# STM32F100_Base_Wireless_1.net
KiCad netlist of a schematic drawn in EAGLE
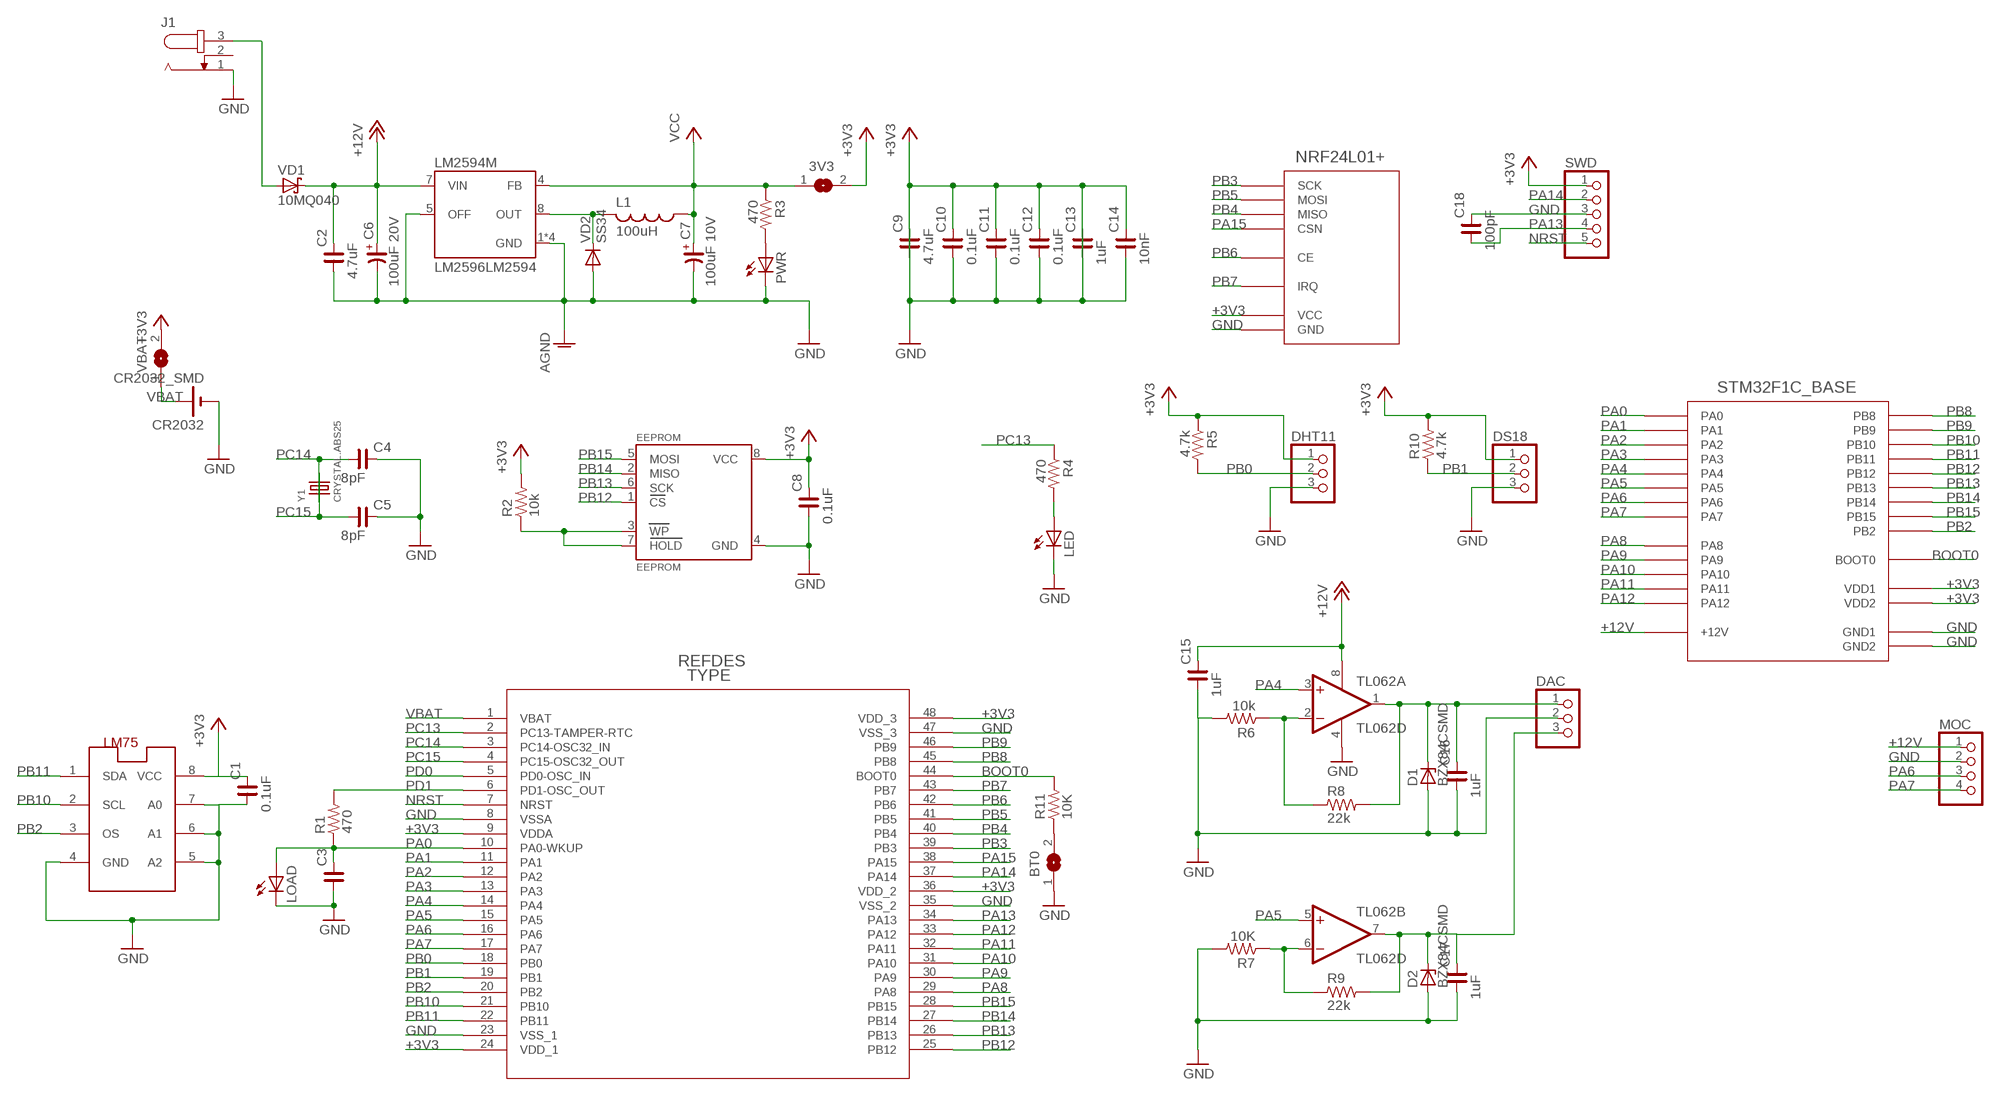
[diagram p0: schematic, sheet 1]

(export (version "E")
  (design (tool "Eeschema 10.0.6"))
  (components
    (comp (ref "3V3") (value "SJ") (footprint "eagle-import:SJ") (libsource (lib "eagle-import") (part "SJ")))
    (comp (ref "BT0") (value "SJ") (footprint "eagle-import:SJ") (libsource (lib "eagle-import") (part "SJ")))
    (comp (ref "C1")
      (value "0.1uF")
      (footprint "eagle-import:C0603")
      (libsource (lib "eagle-import") (part "C_0603"))
    )
    (comp (ref "C2")
      (value "4.7uF")
      (footprint "eagle-import:C0603")
      (libsource (lib "eagle-import") (part "C_0603"))
    )
    (comp (ref "C3")
      (value "C_0603")
      (footprint "eagle-import:C0603")
      (libsource (lib "eagle-import") (part "C_0603"))
    )
    (comp (ref "C4")
      (value "8pF")
      (footprint "eagle-import:C0603")
      (libsource (lib "eagle-import") (part "C_0603"))
    )
    (comp (ref "C5")
      (value "8pF")
      (footprint "eagle-import:C0603")
      (libsource (lib "eagle-import") (part "C_0603"))
    )
    (comp (ref "C6")
      (value "100uF 20V")
      (footprint "eagle-import:C7343_T")
      (libsource (lib "eagle-import") (part "CP_7343"))
    )
    (comp (ref "C7")
      (value "100uF 10V")
      (footprint "eagle-import:C6032-28_T")
      (libsource (lib "eagle-import") (part "CP_6032-28"))
    )
    (comp (ref "C8")
      (value "0.1uF")
      (footprint "eagle-import:C0603")
      (libsource (lib "eagle-import") (part "C_0603"))
    )
    (comp (ref "C9")
      (value "4.7uF")
      (footprint "eagle-import:C0603")
      (libsource (lib "eagle-import") (part "C_0603"))
    )
    (comp (ref "C10")
      (value "0.1uF")
      (footprint "eagle-import:C0603")
      (libsource (lib "eagle-import") (part "C_0603"))
    )
    (comp (ref "C11")
      (value "0.1uF")
      (footprint "eagle-import:C0603")
      (libsource (lib "eagle-import") (part "C_0603"))
    )
    (comp (ref "C12")
      (value "0.1uF")
      (footprint "eagle-import:C0603")
      (libsource (lib "eagle-import") (part "C_0603"))
    )
    (comp (ref "C13")
      (value "1uF")
      (footprint "eagle-import:C0603")
      (libsource (lib "eagle-import") (part "C_0603"))
    )
    (comp (ref "C14")
      (value "10nF")
      (footprint "eagle-import:C0603")
      (libsource (lib "eagle-import") (part "C_0603"))
    )
    (comp (ref "C15")
      (value "1uF")
      (footprint "eagle-import:C0603")
      (libsource (lib "eagle-import") (part "C_0603"))
    )
    (comp (ref "C16")
      (value "1uF")
      (footprint "eagle-import:C0603")
      (libsource (lib "eagle-import") (part "C_0603"))
    )
    (comp (ref "C17")
      (value "1uF")
      (footprint "eagle-import:C0603")
      (libsource (lib "eagle-import") (part "C_0603"))
    )
    (comp (ref "C18")
      (value "100pF")
      (footprint "eagle-import:C0603")
      (libsource (lib "eagle-import") (part "C_0603"))
    )
    (comp (ref "CR2032")
      (value "CR2032_SMD")
      (footprint "eagle-import:SMD_BH-2")
      (libsource (lib "eagle-import") (part "CR2032_SMD"))
    )
    (comp (ref "D1")
      (value "BZX84CSMD")
      (footprint "eagle-import:TO236")
      (libsource (lib "eagle-import") (part "BZX84CSMD"))
    )
    (comp (ref "D2")
      (value "BZX84CSMD")
      (footprint "eagle-import:TO236")
      (libsource (lib "eagle-import") (part "BZX84CSMD"))
    )
    (comp (ref "DAC")
      (value "PINHD-1X03_2.54-S")
      (footprint "eagle-import:1X03-S")
      (libsource (lib "eagle-import") (part "PINHD-1X03_2.54-S"))
    )
    (comp (ref "DHT11")
      (value "PINHD-1X03_2.54-S")
      (footprint "eagle-import:1X03-S")
      (libsource (lib "eagle-import") (part "PINHD-1X03_2.54-S"))
    )
    (comp (ref "DS18")
      (value "PINHD-1X03_2.54-S")
      (footprint "eagle-import:1X03-S")
      (libsource (lib "eagle-import") (part "PINHD-1X03_2.54-S"))
    )
    (comp (ref "EEPROM")
      (value "EEPROM")
      (footprint "eagle-import:SOIC8_150MIL")
      (libsource (lib "eagle-import") (part "EEPROM_SPI_AT25040A"))
    )
    (comp (ref "J1")
      (value "JACK-PLUG0")
      (footprint "eagle-import:SPC4077")
      (libsource (lib "eagle-import") (part "JACK-PLUG0"))
    )
    (comp (ref "L1")
      (value "100uH")
      (footprint "eagle-import:POWER-CHOKE_WE-TPC")
      (libsource (lib "eagle-import") (part "L-USWE-TPC"))
    )
    (comp (ref "LED")
      (value "LEDCHIPLED_1206")
      (footprint "eagle-import:CHIPLED_1206")
      (libsource (lib "eagle-import") (part "LEDCHIPLED_1206"))
    )
    (comp (ref "LM75")
      (value "LM75_ICN")
      (footprint "eagle-import:SO8_LM75")
      (libsource (lib "eagle-import") (part "LM75_ICN"))
    )
    (comp (ref "LM2594M")
      (value "LM2596LM2594")
      (footprint "eagle-import:SOIC8_150MIL")
      (libsource (lib "eagle-import") (part "LM2596LM2594"))
    )
    (comp (ref "LOAD")
      (value "LEDCHIPLED_1206")
      (footprint "eagle-import:CHIPLED_1206")
      (libsource (lib "eagle-import") (part "LEDCHIPLED_1206"))
    )
    (comp (ref "MOC")
      (value "PINHD-1X04_2.54-S")
      (footprint "eagle-import:1X04-S")
      (libsource (lib "eagle-import") (part "PINHD-1X04_2.54-S"))
    )
    (comp (ref "NRF24L01+")
      (value "NRF24L01+")
      (footprint "eagle-import:NRF24L01+")
      (libsource (lib "eagle-import") (part "NRF24L01+"))
    )
    (comp (ref "PWR")
      (value "LEDCHIPLED_1206")
      (footprint "eagle-import:CHIPLED_1206")
      (libsource (lib "eagle-import") (part "LEDCHIPLED_1206"))
    )
    (comp (ref "R1")
      (value "470")
      (footprint "eagle-import:R1206")
      (libsource (lib "eagle-import") (part "R_1206"))
    )
    (comp (ref "R2")
      (value "10k")
      (footprint "eagle-import:R1206")
      (libsource (lib "eagle-import") (part "R_1206"))
    )
    (comp (ref "R3")
      (value "470")
      (footprint "eagle-import:R1206")
      (libsource (lib "eagle-import") (part "R_1206"))
    )
    (comp (ref "R4")
      (value "470")
      (footprint "eagle-import:R1206")
      (libsource (lib "eagle-import") (part "R_1206"))
    )
    (comp (ref "R5")
      (value "4.7k")
      (footprint "eagle-import:R1206")
      (libsource (lib "eagle-import") (part "R_1206"))
    )
    (comp (ref "R6")
      (value "10k")
      (footprint "eagle-import:R1206")
      (libsource (lib "eagle-import") (part "R_1206"))
    )
    (comp (ref "R7")
      (value "10K")
      (footprint "eagle-import:R1206")
      (libsource (lib "eagle-import") (part "R_1206"))
    )
    (comp (ref "R8")
      (value "22k")
      (footprint "eagle-import:R1206")
      (libsource (lib "eagle-import") (part "R_1206"))
    )
    (comp (ref "R9")
      (value "22k")
      (footprint "eagle-import:R1206")
      (libsource (lib "eagle-import") (part "R_1206"))
    )
    (comp (ref "R10")
      (value "4.7k")
      (footprint "eagle-import:R1206")
      (libsource (lib "eagle-import") (part "R_1206"))
    )
    (comp (ref "R11")
      (value "10K")
      (footprint "eagle-import:R1206")
      (libsource (lib "eagle-import") (part "R_1206"))
    )
    (comp (ref "STM32F100C")
      (value "STM32F100C8T6B")
      (footprint "eagle-import:LQFP-48")
      (libsource (lib "eagle-import") (part "STM32F100C8T6B"))
    )
    (comp (ref "SWD")
      (value "PINHD-1X05_2.54-90°-S")
      (footprint "eagle-import:1X05_90-S")
      (libsource (lib "eagle-import") (part "PINHD-1X05_2.54-90°-S"))
    )
    (comp (ref "TL062")
      (value "TL062D")
      (footprint "eagle-import:SO08")
      (libsource (lib "eagle-import") (part "TL062D"))
    )
    (comp (ref "U$1")
      (value "STM32F1C_BASE")
      (footprint "eagle-import:STM32F1_BASE")
      (libsource (lib "eagle-import") (part "STM32F1C_BASE"))
    )
    (comp (ref "VBAT")
      (value "SJ")
      (footprint "eagle-import:SJ")
      (libsource (lib "eagle-import") (part "SJ"))
    )
    (comp (ref "VD1")
      (value "10MQ040")
      (footprint "eagle-import:SMA")
      (libsource (lib "eagle-import") (part "10MQ040"))
    )
    (comp (ref "VD2")
      (value "SS34")
      (footprint "eagle-import:DO214AC")
      (libsource (lib "eagle-import") (part "DIODE-DO214AC"))
    )
    (comp (ref "Y1")
      (value "CRYSTAL.ABS25")
      (footprint "eagle-import:ABS25")
      (libsource (lib "eagle-import") (part "CRYSTAL.ABS25"))
    )
  )
  (nets
    (net (code "1") (name "+3V3") (class "Default")
      (node (ref "3V3") (pin "2") (pinfunction "2_2") (pintype "passive"))
      (node (ref "C1") (pin "2") (pinfunction "2_2") (pintype "passive"))
      (node (ref "C10") (pin "2") (pinfunction "2_2") (pintype "passive"))
      (node (ref "C11") (pin "2") (pinfunction "2_2") (pintype "passive"))
      (node (ref "C12") (pin "2") (pinfunction "2_2") (pintype "passive"))
      (node (ref "C13") (pin "1") (pinfunction "1_1") (pintype "passive"))
      (node (ref "C14") (pin "2") (pinfunction "2_2") (pintype "passive"))
      (node (ref "C8") (pin "2") (pinfunction "2_2") (pintype "passive"))
      (node (ref "C9") (pin "1") (pinfunction "1_1") (pintype "passive"))
      (node (ref "DHT11") (pin "1") (pinfunction "1_1") (pintype "passive"))
      (node (ref "DS18") (pin "1") (pinfunction "1_1") (pintype "passive"))
      (node (ref "EEPROM") (pin "8") (pinfunction "VCC_8") (pintype "power_in"))
      (node (ref "LM75") (pin "8") (pinfunction "VCC_8") (pintype "power_in"))
      (node (ref "NRF24L01+") (pin "VCC") (pinfunction "VCC_VCC") (pintype "passive"))
      (node (ref "R10") (pin "2") (pinfunction "2_2") (pintype "passive"))
      (node (ref "R2") (pin "2") (pinfunction "2_2") (pintype "passive"))
      (node (ref "R5") (pin "1") (pinfunction "1_1") (pintype "passive"))
      (node (ref "STM32F100C") (pin "24") (pinfunction "VDD_1_24") (pintype "passive"))
      (node (ref "STM32F100C") (pin "36") (pinfunction "VDD_2_36") (pintype "passive"))
      (node (ref "STM32F100C") (pin "48") (pinfunction "VDD_3_48") (pintype "passive"))
      (node (ref "STM32F100C") (pin "9") (pinfunction "VDDA_9") (pintype "passive"))
      (node (ref "SWD") (pin "1") (pinfunction "1_1") (pintype "passive"))
      (node (ref "U$1") (pin "3.3") (pinfunction "VDD1_3.3") (pintype "power_in"))
      (node (ref "U$1") (pin "3.3_1") (pinfunction "VDD2_3.3_1") (pintype "power_in"))
      (node (ref "VBAT") (pin "2") (pinfunction "2_2") (pintype "passive"))
    )
    (net (code "2") (name "+12V") (class "Default")
      (node (ref "C15") (pin "2") (pinfunction "2_2") (pintype "passive"))
      (node (ref "C2") (pin "2") (pinfunction "2_2") (pintype "passive"))
      (node (ref "C6") (pin "+") (pinfunction "+_+") (pintype "passive"))
      (node (ref "LM2594M") (pin "7") (pinfunction "VIN_7") (pintype "power_in"))
      (node (ref "MOC") (pin "1") (pinfunction "1_1") (pintype "passive"))
      (node (ref "TL062") (pin "8") (pinfunction "V+_8") (pintype "power_in"))
      (node (ref "U$1") (pin "+12") (pinfunction "+12V_+12") (pintype "power_in"))
      (node (ref "VD1") (pin "C") (pinfunction "C_C") (pintype "passive"))
    )
    (net (code "3") (name "/BOOT0") (class "Default")
      (node (ref "R11") (pin "2") (pinfunction "2_2") (pintype "passive"))
      (node (ref "STM32F100C") (pin "44") (pinfunction "BOOT0_44") (pintype "passive"))
      (node (ref "U$1") (pin "BOOT0") (pinfunction "BOOT0_BOOT0") (pintype "passive"))
    )
    (net (code "4") (name "/NRST") (class "Default")
      (node (ref "STM32F100C") (pin "7") (pinfunction "NRST_7") (pintype "passive"))
      (node (ref "SWD") (pin "5") (pinfunction "5_5") (pintype "passive"))
    )
    (net (code "5") (name "/PA0") (class "Default")
      (node (ref "C3") (pin "2") (pinfunction "2_2") (pintype "passive"))
      (node (ref "LOAD") (pin "A") (pinfunction "A_A") (pintype "passive"))
      (node (ref "R1") (pin "1") (pinfunction "1_1") (pintype "passive"))
      (node (ref "STM32F100C") (pin "10") (pinfunction "PA0-WKUP_10") (pintype "passive"))
      (node (ref "U$1") (pin "PA0") (pinfunction "PA0_PA0") (pintype "passive"))
    )
    (net (code "6") (name "/PA1") (class "Default")
      (node (ref "STM32F100C") (pin "11") (pinfunction "PA1_11") (pintype "passive"))
      (node (ref "U$1") (pin "PA1") (pinfunction "PA1_PA1") (pintype "passive"))
    )
    (net (code "7") (name "/PA2") (class "Default")
      (node (ref "STM32F100C") (pin "12") (pinfunction "PA2_12") (pintype "passive"))
      (node (ref "U$1") (pin "PA2") (pinfunction "PA2_PA2") (pintype "passive"))
    )
    (net (code "8") (name "/PA3") (class "Default")
      (node (ref "STM32F100C") (pin "13") (pinfunction "PA3_13") (pintype "passive"))
      (node (ref "U$1") (pin "PA3") (pinfunction "PA3_PA3") (pintype "passive"))
    )
    (net (code "9") (name "/PA4") (class "Default")
      (node (ref "STM32F100C") (pin "14") (pinfunction "PA4_14") (pintype "passive"))
      (node (ref "TL062") (pin "3") (pinfunction "+IN_3") (pintype "input"))
      (node (ref "U$1") (pin "PA4") (pinfunction "PA4_PA4") (pintype "passive"))
    )
    (net (code "10") (name "/PA5") (class "Default")
      (node (ref "STM32F100C") (pin "15") (pinfunction "PA5_15") (pintype "passive"))
      (node (ref "TL062") (pin "5") (pinfunction "+IN_5") (pintype "input"))
      (node (ref "U$1") (pin "PA5") (pinfunction "PA5_PA5") (pintype "passive"))
    )
    (net (code "11") (name "/PA6") (class "Default")
      (node (ref "MOC") (pin "3") (pinfunction "3_3") (pintype "passive"))
      (node (ref "STM32F100C") (pin "16") (pinfunction "PA6_16") (pintype "passive"))
      (node (ref "U$1") (pin "PA6") (pinfunction "PA6_PA6") (pintype "passive"))
    )
    (net (code "12") (name "/PA7") (class "Default")
      (node (ref "MOC") (pin "4") (pinfunction "4_4") (pintype "passive"))
      (node (ref "STM32F100C") (pin "17") (pinfunction "PA7_17") (pintype "passive"))
      (node (ref "U$1") (pin "PA7") (pinfunction "PA7_PA7") (pintype "passive"))
    )
    (net (code "13") (name "/PA8") (class "Default")
      (node (ref "STM32F100C") (pin "29") (pinfunction "PA8_29") (pintype "passive"))
      (node (ref "U$1") (pin "PA8") (pinfunction "PA8_PA8") (pintype "passive"))
    )
    (net (code "14") (name "/PA9") (class "Default")
      (node (ref "STM32F100C") (pin "30") (pinfunction "PA9_30") (pintype "passive"))
      (node (ref "U$1") (pin "PA9") (pinfunction "PA9_PA9") (pintype "passive"))
    )
    (net (code "15") (name "/PA10") (class "Default")
      (node (ref "STM32F100C") (pin "31") (pinfunction "PA10_31") (pintype "passive"))
      (node (ref "U$1") (pin "PA10") (pinfunction "PA10_PA10") (pintype "passive"))
    )
    (net (code "16") (name "/PA11") (class "Default")
      (node (ref "STM32F100C") (pin "32") (pinfunction "PA11_32") (pintype "passive"))
      (node (ref "U$1") (pin "PA11") (pinfunction "PA11_PA11") (pintype "passive"))
    )
    (net (code "17") (name "/PA12") (class "Default")
      (node (ref "STM32F100C") (pin "33") (pinfunction "PA12_33") (pintype "passive"))
      (node (ref "U$1") (pin "PA12") (pinfunction "PA12_PA12") (pintype "passive"))
    )
    (net (code "18") (name "/PA13") (class "Default")
      (node (ref "C18") (pin "1") (pinfunction "1_1") (pintype "passive"))
      (node (ref "STM32F100C") (pin "34") (pinfunction "PA13_34") (pintype "passive"))
      (node (ref "SWD") (pin "4") (pinfunction "4_4") (pintype "passive"))
    )
    (net (code "19") (name "/PA14") (class "Default")
      (node (ref "STM32F100C") (pin "37") (pinfunction "PA14_37") (pintype "passive"))
      (node (ref "SWD") (pin "2") (pinfunction "2_2") (pintype "passive"))
    )
    (net (code "20") (name "/PA15") (class "Default")
      (node (ref "NRF24L01+") (pin "CSN") (pinfunction "CSN_CSN") (pintype "passive"))
      (node (ref "STM32F100C") (pin "38") (pinfunction "PA15_38") (pintype "passive"))
    )
    (net (code "21") (name "/PB0") (class "Default")
      (node (ref "DHT11") (pin "2") (pinfunction "2_2") (pintype "passive"))
      (node (ref "R5") (pin "2") (pinfunction "2_2") (pintype "passive"))
      (node (ref "STM32F100C") (pin "18") (pinfunction "PB0_18") (pintype "passive"))
    )
    (net (code "22") (name "/PB1") (class "Default")
      (node (ref "DS18") (pin "2") (pinfunction "2_2") (pintype "passive"))
      (node (ref "R10") (pin "1") (pinfunction "1_1") (pintype "passive"))
      (node (ref "STM32F100C") (pin "19") (pinfunction "PB1_19") (pintype "passive"))
    )
    (net (code "23") (name "/PB2") (class "Default")
      (node (ref "LM75") (pin "3") (pinfunction "OS_3") (pintype "output"))
      (node (ref "STM32F100C") (pin "20") (pinfunction "PB2_20") (pintype "passive"))
      (node (ref "U$1") (pin "B2") (pinfunction "PB2_B2") (pintype "passive"))
    )
    (net (code "24") (name "/PB3") (class "Default")
      (node (ref "NRF24L01+") (pin "SCK") (pinfunction "SCK_SCK") (pintype "passive"))
      (node (ref "STM32F100C") (pin "39") (pinfunction "PB3_39") (pintype "passive"))
    )
    (net (code "25") (name "/PB4") (class "Default")
      (node (ref "NRF24L01+") (pin "MISO") (pinfunction "MISO_MISO") (pintype "passive"))
      (node (ref "STM32F100C") (pin "40") (pinfunction "PB4_40") (pintype "passive"))
    )
    (net (code "26") (name "/PB5") (class "Default")
      (node (ref "NRF24L01+") (pin "MOSI") (pinfunction "MOSI_MOSI") (pintype "passive"))
      (node (ref "STM32F100C") (pin "41") (pinfunction "PB5_41") (pintype "passive"))
    )
    (net (code "27") (name "/PB6") (class "Default")
      (node (ref "NRF24L01+") (pin "CE") (pinfunction "CE_CE") (pintype "passive"))
      (node (ref "STM32F100C") (pin "42") (pinfunction "PB6_42") (pintype "passive"))
    )
    (net (code "28") (name "/PB7") (class "Default")
      (node (ref "NRF24L01+") (pin "IRQ") (pinfunction "IRQ_IRQ") (pintype "passive"))
      (node (ref "STM32F100C") (pin "43") (pinfunction "PB7_43") (pintype "passive"))
    )
    (net (code "29") (name "/PB8") (class "Default")
      (node (ref "STM32F100C") (pin "45") (pinfunction "PB8_45") (pintype "passive"))
      (node (ref "U$1") (pin "PB8") (pinfunction "PB8_PB8") (pintype "passive"))
    )
    (net (code "30") (name "/PB9") (class "Default")
      (node (ref "STM32F100C") (pin "46") (pinfunction "PB9_46") (pintype "passive"))
      (node (ref "U$1") (pin "PB9") (pinfunction "PB9_PB9") (pintype "passive"))
    )
    (net (code "31") (name "/PB10") (class "Default")
      (node (ref "LM75") (pin "2") (pinfunction "SCL_2") (pintype "bidirectional"))
      (node (ref "STM32F100C") (pin "21") (pinfunction "PB10_21") (pintype "passive"))
      (node (ref "U$1") (pin "PB10") (pinfunction "PB10_PB10") (pintype "passive"))
    )
    (net (code "32") (name "/PB11") (class "Default")
      (node (ref "LM75") (pin "1") (pinfunction "SDA_1") (pintype "bidirectional"))
      (node (ref "STM32F100C") (pin "22") (pinfunction "PB11_22") (pintype "passive"))
      (node (ref "U$1") (pin "PB11") (pinfunction "PB11_PB11") (pintype "passive"))
    )
    (net (code "33") (name "/PB12") (class "Default")
      (node (ref "EEPROM") (pin "1") (pinfunction "CS_1") (pintype "bidirectional"))
      (node (ref "STM32F100C") (pin "25") (pinfunction "PB12_25") (pintype "passive"))
      (node (ref "U$1") (pin "PB12") (pinfunction "PB12_PB12") (pintype "passive"))
    )
    (net (code "34") (name "/PB13") (class "Default")
      (node (ref "EEPROM") (pin "6") (pinfunction "SCK_6") (pintype "bidirectional"))
      (node (ref "STM32F100C") (pin "26") (pinfunction "PB13_26") (pintype "passive"))
      (node (ref "U$1") (pin "PB13") (pinfunction "PB13_PB13") (pintype "passive"))
    )
    (net (code "35") (name "/PB14") (class "Default")
      (node (ref "EEPROM") (pin "2") (pinfunction "MISO_2") (pintype "bidirectional"))
      (node (ref "STM32F100C") (pin "27") (pinfunction "PB14_27") (pintype "passive"))
      (node (ref "U$1") (pin "PB14") (pinfunction "PB14_PB14") (pintype "passive"))
    )
    (net (code "36") (name "/PB15") (class "Default")
      (node (ref "EEPROM") (pin "5") (pinfunction "MOSI_5") (pintype "bidirectional"))
      (node (ref "STM32F100C") (pin "28") (pinfunction "PB15_28") (pintype "passive"))
      (node (ref "U$1") (pin "PB15") (pinfunction "PB15_PB15") (pintype "passive"))
    )
    (net (code "37") (name "/PC13") (class "Default")
      (node (ref "R4") (pin "1") (pinfunction "1_1") (pintype "passive"))
      (node (ref "STM32F100C") (pin "2") (pinfunction "PC13-TAMPER-RTC_2") (pintype "passive"))
    )
    (net (code "38") (name "/PC14") (class "Default")
      (node (ref "C4") (pin "1") (pinfunction "1_1") (pintype "passive"))
      (node (ref "STM32F100C") (pin "3") (pinfunction "PC14-OSC32_IN_3") (pintype "passive"))
      (node (ref "Y1") (pin "1") (pinfunction "1_1") (pintype "passive"))
    )
    (net (code "39") (name "/PC15") (class "Default")
      (node (ref "C5") (pin "1") (pinfunction "1_1") (pintype "passive"))
      (node (ref "STM32F100C") (pin "4") (pinfunction "PC15-OSC32_OUT_4") (pintype "passive"))
      (node (ref "Y1") (pin "4") (pinfunction "2_4") (pintype "passive"))
    )
    (net (code "40") (name "/PD0") (class "Default")
      (node (ref "STM32F100C") (pin "5") (pinfunction "PD0-OSC_IN_5") (pintype "passive"))
    )
    (net (code "41") (name "/PD1") (class "Default")
      (node (ref "R1") (pin "2") (pinfunction "2_2") (pintype "passive"))
      (node (ref "STM32F100C") (pin "6") (pinfunction "PD1-OSC_OUT_6") (pintype "passive"))
    )
    (net (code "42") (name "/VBAT") (class "Default")
      (node (ref "CR2032") (pin "P$POS1") (pinfunction "+_P$POS1") (pintype "passive"))
      (node (ref "STM32F100C") (pin "1") (pinfunction "VBAT_1") (pintype "passive"))
      (node (ref "VBAT") (pin "1") (pinfunction "1_1") (pintype "passive"))
    )
    (net (code "43") (name "AGND") (class "Default")
      (node (ref "BT0") (pin "1") (pinfunction "1_1") (pintype "passive"))
      (node (ref "C1") (pin "1") (pinfunction "1_1") (pintype "passive"))
      (node (ref "C10") (pin "1") (pinfunction "1_1") (pintype "passive"))
      (node (ref "C11") (pin "1") (pinfunction "1_1") (pintype "passive"))
      (node (ref "C12") (pin "1") (pinfunction "1_1") (pintype "passive"))
      (node (ref "C13") (pin "2") (pinfunction "2_2") (pintype "passive"))
      (node (ref "C14") (pin "1") (pinfunction "1_1") (pintype "passive"))
      (node (ref "C15") (pin "1") (pinfunction "1_1") (pintype "passive"))
      (node (ref "C16") (pin "1") (pinfunction "1_1") (pintype "passive"))
      (node (ref "C17") (pin "1") (pinfunction "1_1") (pintype "passive"))
      (node (ref "C18") (pin "2") (pinfunction "2_2") (pintype "passive"))
      (node (ref "C2") (pin "1") (pinfunction "1_1") (pintype "passive"))
      (node (ref "C3") (pin "1") (pinfunction "1_1") (pintype "passive"))
      (node (ref "C4") (pin "2") (pinfunction "2_2") (pintype "passive"))
      (node (ref "C5") (pin "2") (pinfunction "2_2") (pintype "passive"))
      (node (ref "C6") (pin "-") (pinfunction "-_-") (pintype "passive"))
      (node (ref "C7") (pin "-") (pinfunction "-_-") (pintype "passive"))
      (node (ref "C8") (pin "1") (pinfunction "1_1") (pintype "passive"))
      (node (ref "C9") (pin "2") (pinfunction "2_2") (pintype "passive"))
      (node (ref "CR2032") (pin "P$NEG") (pinfunction "-_P$NEG") (pintype "passive"))
      (node (ref "D1") (pin "A") (pinfunction "A_A") (pintype "passive"))
      (node (ref "D2") (pin "A") (pinfunction "A_A") (pintype "passive"))
      (node (ref "DAC") (pin "2") (pinfunction "2_2") (pintype "passive"))
      (node (ref "DHT11") (pin "3") (pinfunction "3_3") (pintype "passive"))
      (node (ref "DS18") (pin "3") (pinfunction "3_3") (pintype "passive"))
      (node (ref "EEPROM") (pin "4") (pinfunction "GND_4") (pintype "power_in"))
      (node (ref "J1") (pin "1") (pinfunction "1_1") (pintype "passive"))
      (node (ref "LED") (pin "C") (pinfunction "C_C") (pintype "passive"))
      (node (ref "LM2594M") (pin "1") (pinfunction "GND_1") (pintype "power_in"))
      (node (ref "LM2594M") (pin "2") (pinfunction "GND_2") (pintype "power_in"))
      (node (ref "LM2594M") (pin "3") (pinfunction "GND_3") (pintype "power_in"))
      (node (ref "LM2594M") (pin "5") (pinfunction "OFF_5") (pintype "input"))
      (node (ref "LM2594M") (pin "6") (pinfunction "GND_6") (pintype "power_in"))
      (node (ref "LM75") (pin "4") (pinfunction "GND_4") (pintype "power_in"))
      (node (ref "LM75") (pin "5") (pinfunction "A2_5") (pintype "input"))
      (node (ref "LM75") (pin "6") (pinfunction "A1_6") (pintype "input"))
      (node (ref "LM75") (pin "7") (pinfunction "A0_7") (pintype "input"))
      (node (ref "LOAD") (pin "C") (pinfunction "C_C") (pintype "passive"))
      (node (ref "MOC") (pin "2") (pinfunction "2_2") (pintype "passive"))
      (node (ref "NRF24L01+") (pin "GND") (pinfunction "GND_GND") (pintype "passive"))
      (node (ref "PWR") (pin "C") (pinfunction "C_C") (pintype "passive"))
      (node (ref "R6") (pin "2") (pinfunction "2_2") (pintype "passive"))
      (node (ref "R7") (pin "2") (pinfunction "2_2") (pintype "passive"))
      (node (ref "STM32F100C") (pin "23") (pinfunction "VSS_1_23") (pintype "passive"))
      (node (ref "STM32F100C") (pin "35") (pinfunction "VSS_2_35") (pintype "passive"))
      (node (ref "STM32F100C") (pin "47") (pinfunction "VSS_3_47") (pintype "passive"))
      (node (ref "STM32F100C") (pin "8") (pinfunction "VSSA_8") (pintype "passive"))
      (node (ref "SWD") (pin "3") (pinfunction "3_3") (pintype "passive"))
      (node (ref "TL062") (pin "4") (pinfunction "V-_4") (pintype "power_in"))
      (node (ref "U$1") (pin "GND") (pinfunction "GND1_GND") (pintype "power_in"))
      (node (ref "U$1") (pin "GND1") (pinfunction "GND2_GND1") (pintype "power_in"))
      (node (ref "VD2") (pin "A") (pinfunction "A_A") (pintype "passive"))
    )
    (net (code "44") (name "Net-(BT0-Pad2)") (class "Default")
      (node (ref "BT0") (pin "2") (pinfunction "2_2") (pintype "passive"))
      (node (ref "R11") (pin "1") (pinfunction "1_1") (pintype "passive"))
    )
    (net (code "45") (name "Net-(EEPROM-HOLD)") (class "Default")
      (node (ref "EEPROM") (pin "3") (pinfunction "WP_3") (pintype "bidirectional"))
      (node (ref "EEPROM") (pin "7") (pinfunction "HOLD_7") (pintype "bidirectional"))
      (node (ref "R2") (pin "1") (pinfunction "1_1") (pintype "passive"))
    )
    (net (code "46") (name "Net-(J1-Pad3)") (class "Default")
      (node (ref "J1") (pin "3") (pinfunction "3_3") (pintype "passive"))
      (node (ref "VD1") (pin "A") (pinfunction "A_A") (pintype "passive"))
    )
    (net (code "47") (name "Net-(LED-PadA)") (class "Default")
      (node (ref "LED") (pin "A") (pinfunction "A_A") (pintype "passive"))
      (node (ref "R4") (pin "2") (pinfunction "2_2") (pintype "passive"))
    )
    (net (code "48") (name "Net-(LM2594M-OUT)") (class "Default")
      (node (ref "L1") (pin "2") (pinfunction "2_2") (pintype "passive"))
      (node (ref "LM2594M") (pin "8") (pinfunction "OUT_8") (pintype "output"))
      (node (ref "VD2") (pin "C") (pinfunction "C_C") (pintype "passive"))
    )
    (net (code "49") (name "Net-(PWR-PadA)") (class "Default")
      (node (ref "PWR") (pin "A") (pinfunction "A_A") (pintype "passive"))
      (node (ref "R3") (pin "2") (pinfunction "2_2") (pintype "passive"))
    )
    (net (code "50") (name "Net-(TL062A--IN)") (class "Default")
      (node (ref "R6") (pin "1") (pinfunction "1_1") (pintype "passive"))
      (node (ref "R8") (pin "1") (pinfunction "1_1") (pintype "passive"))
      (node (ref "TL062") (pin "2") (pinfunction "-IN_2") (pintype "input"))
    )
    (net (code "51") (name "Net-(TL062A-OUT)") (class "Default")
      (node (ref "C16") (pin "2") (pinfunction "2_2") (pintype "passive"))
      (node (ref "D1") (pin "C") (pinfunction "C_C") (pintype "passive"))
      (node (ref "DAC") (pin "1") (pinfunction "1_1") (pintype "passive"))
      (node (ref "R8") (pin "2") (pinfunction "2_2") (pintype "passive"))
      (node (ref "TL062") (pin "1") (pinfunction "OUT_1") (pintype "output"))
    )
    (net (code "52") (name "Net-(TL062B--IN)") (class "Default")
      (node (ref "R7") (pin "1") (pinfunction "1_1") (pintype "passive"))
      (node (ref "R9") (pin "1") (pinfunction "1_1") (pintype "passive"))
      (node (ref "TL062") (pin "6") (pinfunction "-IN_6") (pintype "input"))
    )
    (net (code "53") (name "Net-(TL062B-OUT)") (class "Default")
      (node (ref "C17") (pin "2") (pinfunction "2_2") (pintype "passive"))
      (node (ref "D2") (pin "C") (pinfunction "C_C") (pintype "passive"))
      (node (ref "DAC") (pin "3") (pinfunction "3_3") (pintype "passive"))
      (node (ref "R9") (pin "2") (pinfunction "2_2") (pintype "passive"))
      (node (ref "TL062") (pin "7") (pinfunction "OUT_7") (pintype "output"))
    )
    (net (code "54") (name "VCC") (class "Default")
      (node (ref "3V3") (pin "1") (pinfunction "1_1") (pintype "passive"))
      (node (ref "C7") (pin "+") (pinfunction "+_+") (pintype "passive"))
      (node (ref "L1") (pin "1") (pinfunction "1_1") (pintype "passive"))
      (node (ref "LM2594M") (pin "4") (pinfunction "FB_4") (pintype "input"))
      (node (ref "R3") (pin "1") (pinfunction "1_1") (pintype "passive"))
    )
    (net (code "55") (name "unconnected-(J1-Pad2)") (class "Default")
      (node (ref "J1") (pin "2") (pinfunction "2_2") (pintype "passive"))
    )
  )
)
